# keyboard-Right.net
KiCad netlist of a schematic drawn in Altium Designer
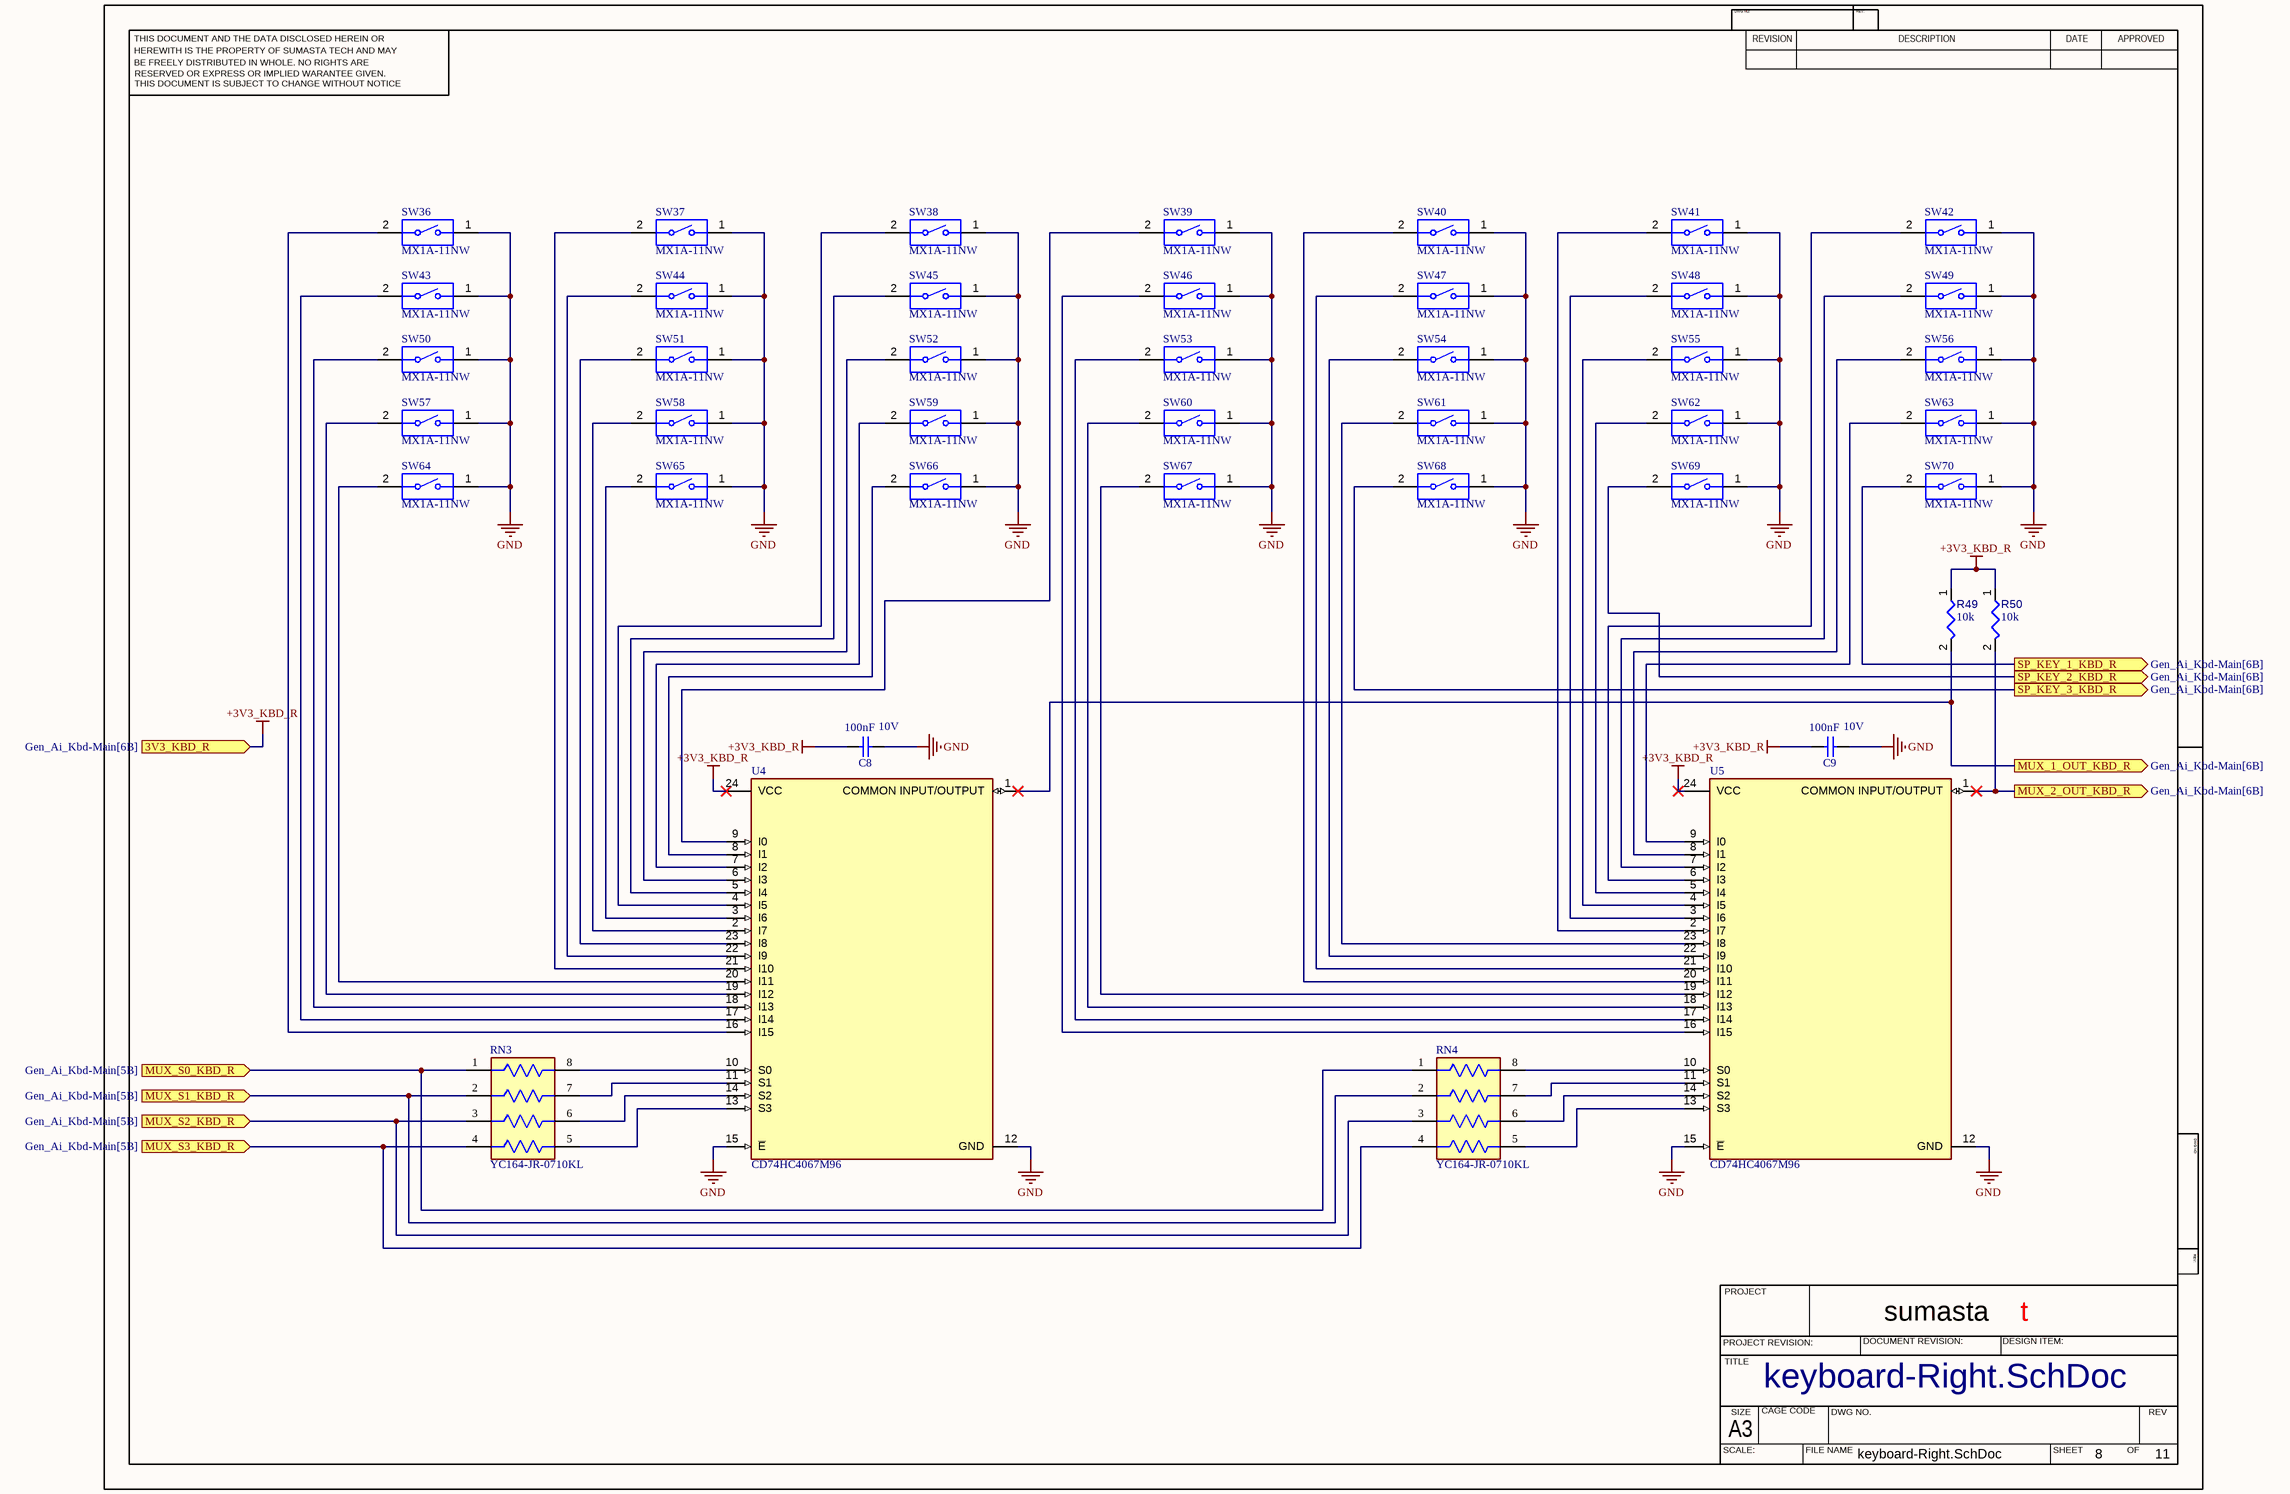
[diagram p0: keyboard-Right.SchDoc]

(export (version "E")
  (design (tool "Eeschema 10.0.6"))
  (components
    (comp (ref "C8")
      (value "885012206020")
      (footprint "WCAP-CSGP_0603_L1.6W0.8H0.8_Reflow")
      (description "WCAP-CSGP Multilayer Ceramic Chip Capacitor, General Purpose, size 0603, X7R, 100nF, 10VDC")
      (fields
        (field (name "MANUFACTURER") "Wurth Elektronik")
        (field (name "RATED VOLTAGE (DC)") "10V")
        (field (name "CAPACITANCE") "100nF")
      )
      (libsource (lib "Test365") (part "885012209047R"))
    )
    (comp (ref "C9")
      (value "885012206020")
      (footprint "WCAP-CSGP_0603_L1.6W0.8H0.8_Reflow")
      (description "WCAP-CSGP Multilayer Ceramic Chip Capacitor, General Purpose, size 0603, X7R, 100nF, 10VDC")
      (fields
        (field (name "MANUFACTURER") "Wurth Elektronik")
        (field (name "RATED VOLTAGE (DC)") "10V")
        (field (name "CAPACITANCE") "100nF")
      )
      (libsource (lib "Test365") (part "885012209047R"))
    )
    (comp (ref "R49")
      (value "10k")
      (footprint "RESC1608X55X25ML10T15")
      (description "Chip Resistor, 10 KOhm, +/- 1%, 01 W, -55 to 155 degC, 0603 (1608 Metric)")
      (fields (field (name "POWER") "100mW") (field (name "TOLERANCE") "1%"))
      (libsource (lib "Test365") (part "RES-2"))
    )
    (comp (ref "R50")
      (value "10k")
      (footprint "RESC1608X55X25ML10T15")
      (description "Chip Resistor, 10 KOhm, +/- 1%, 01 W, -55 to 155 degC, 0603 (1608 Metric)")
      (fields (field (name "POWER") "100mW") (field (name "TOLERANCE") "1%"))
      (libsource (lib "Test365") (part "RES-2"))
    )
    (comp (ref "RN3")
      (value "YC164-JR-0710KL")
      (footprint "FP-YC164-MFG")
      (description "RES ARRAY 4 RES 10K OHM 1206")
      (fields (field (name "TOLERANCE") "1%"))
      (libsource (lib "Altium Content Vault") (part "deefe693e103177f92eb02ee49083c3"))
    )
    (comp (ref "RN4")
      (value "YC164-JR-0710KL")
      (footprint "FP-YC164-MFG")
      (description "RES ARRAY 4 RES 10K OHM 1206")
      (fields (field (name "TOLERANCE") "1%"))
      (libsource (lib "Altium Content Vault") (part "deefe693e103177f92eb02ee49083c3"))
    )
    (comp (ref "SW36")
      (value "MX1A-11NW")
      (footprint "CHRY-MX1A-11NW_V")
      (description "Switch Key N.O. SPST 0.01A 12VAC 12VDC 0.58N PC Pins 50000000Cycles Thru-Hole")
      (libsource (lib "Test365") (part "KEYSW-SPST-2"))
    )
    (comp (ref "SW37")
      (value "MX1A-11NW")
      (footprint "CHRY-MX1A-11NW_V")
      (description "Switch Key N.O. SPST 0.01A 12VAC 12VDC 0.58N PC Pins 50000000Cycles Thru-Hole")
      (libsource (lib "Test365") (part "KEYSW-SPST-2"))
    )
    (comp (ref "SW38")
      (value "MX1A-11NW")
      (footprint "CHRY-MX1A-11NW_V")
      (description "Switch Key N.O. SPST 0.01A 12VAC 12VDC 0.58N PC Pins 50000000Cycles Thru-Hole")
      (libsource (lib "Test365") (part "KEYSW-SPST-2"))
    )
    (comp (ref "SW39")
      (value "MX1A-11NW")
      (footprint "CHRY-MX1A-11NW_V")
      (description "Switch Key N.O. SPST 0.01A 12VAC 12VDC 0.58N PC Pins 50000000Cycles Thru-Hole")
      (libsource (lib "Test365") (part "KEYSW-SPST-2"))
    )
    (comp (ref "SW40")
      (value "MX1A-11NW")
      (footprint "CHRY-MX1A-11NW_V")
      (description "Switch Key N.O. SPST 0.01A 12VAC 12VDC 0.58N PC Pins 50000000Cycles Thru-Hole")
      (libsource (lib "Test365") (part "KEYSW-SPST-2"))
    )
    (comp (ref "SW41")
      (value "MX1A-11NW")
      (footprint "CHRY-MX1A-11NW_V")
      (description "Switch Key N.O. SPST 0.01A 12VAC 12VDC 0.58N PC Pins 50000000Cycles Thru-Hole")
      (libsource (lib "Test365") (part "KEYSW-SPST-2"))
    )
    (comp (ref "SW42")
      (value "MX1A-11NW")
      (footprint "CHRY-MX1A-11NW_V")
      (description "Switch Key N.O. SPST 0.01A 12VAC 12VDC 0.58N PC Pins 50000000Cycles Thru-Hole")
      (libsource (lib "Test365") (part "KEYSW-SPST-2"))
    )
    (comp (ref "SW43")
      (value "MX1A-11NW")
      (footprint "CHRY-MX1A-11NW_V")
      (description "Switch Key N.O. SPST 0.01A 12VAC 12VDC 0.58N PC Pins 50000000Cycles Thru-Hole")
      (libsource (lib "Test365") (part "KEYSW-SPST-2"))
    )
    (comp (ref "SW44")
      (value "MX1A-11NW")
      (footprint "CHRY-MX1A-11NW_V")
      (description "Switch Key N.O. SPST 0.01A 12VAC 12VDC 0.58N PC Pins 50000000Cycles Thru-Hole")
      (libsource (lib "Test365") (part "KEYSW-SPST-2"))
    )
    (comp (ref "SW45")
      (value "MX1A-11NW")
      (footprint "CHRY-MX1A-11NW_V")
      (description "Switch Key N.O. SPST 0.01A 12VAC 12VDC 0.58N PC Pins 50000000Cycles Thru-Hole")
      (libsource (lib "Test365") (part "KEYSW-SPST-2"))
    )
    (comp (ref "SW46")
      (value "MX1A-11NW")
      (footprint "CHRY-MX1A-11NW_V")
      (description "Switch Key N.O. SPST 0.01A 12VAC 12VDC 0.58N PC Pins 50000000Cycles Thru-Hole")
      (libsource (lib "Test365") (part "KEYSW-SPST-2"))
    )
    (comp (ref "SW47")
      (value "MX1A-11NW")
      (footprint "CHRY-MX1A-11NW_V")
      (description "Switch Key N.O. SPST 0.01A 12VAC 12VDC 0.58N PC Pins 50000000Cycles Thru-Hole")
      (libsource (lib "Test365") (part "KEYSW-SPST-2"))
    )
    (comp (ref "SW48")
      (value "MX1A-11NW")
      (footprint "CHRY-MX1A-11NW_V")
      (description "Switch Key N.O. SPST 0.01A 12VAC 12VDC 0.58N PC Pins 50000000Cycles Thru-Hole")
      (libsource (lib "Test365") (part "KEYSW-SPST-2"))
    )
    (comp (ref "SW49")
      (value "MX1A-11NW")
      (footprint "CHRY-MX1A-11NW_V")
      (description "Switch Key N.O. SPST 0.01A 12VAC 12VDC 0.58N PC Pins 50000000Cycles Thru-Hole")
      (libsource (lib "Test365") (part "KEYSW-SPST-2"))
    )
    (comp (ref "SW50")
      (value "MX1A-11NW")
      (footprint "CHRY-MX1A-11NW_V")
      (description "Switch Key N.O. SPST 0.01A 12VAC 12VDC 0.58N PC Pins 50000000Cycles Thru-Hole")
      (libsource (lib "Test365") (part "KEYSW-SPST-2"))
    )
    (comp (ref "SW51")
      (value "MX1A-11NW")
      (footprint "CHRY-MX1A-11NW_V")
      (description "Switch Key N.O. SPST 0.01A 12VAC 12VDC 0.58N PC Pins 50000000Cycles Thru-Hole")
      (libsource (lib "Test365") (part "KEYSW-SPST-2"))
    )
    (comp (ref "SW52")
      (value "MX1A-11NW")
      (footprint "CHRY-MX1A-11NW_V")
      (description "Switch Key N.O. SPST 0.01A 12VAC 12VDC 0.58N PC Pins 50000000Cycles Thru-Hole")
      (libsource (lib "Test365") (part "KEYSW-SPST-2"))
    )
    (comp (ref "SW53")
      (value "MX1A-11NW")
      (footprint "CHRY-MX1A-11NW_V")
      (description "Switch Key N.O. SPST 0.01A 12VAC 12VDC 0.58N PC Pins 50000000Cycles Thru-Hole")
      (libsource (lib "Test365") (part "KEYSW-SPST-2"))
    )
    (comp (ref "SW54")
      (value "MX1A-11NW")
      (footprint "CHRY-MX1A-11NW_V")
      (description "Switch Key N.O. SPST 0.01A 12VAC 12VDC 0.58N PC Pins 50000000Cycles Thru-Hole")
      (libsource (lib "Test365") (part "KEYSW-SPST-2"))
    )
    (comp (ref "SW55")
      (value "MX1A-11NW")
      (footprint "CHRY-MX1A-11NW_V")
      (description "Switch Key N.O. SPST 0.01A 12VAC 12VDC 0.58N PC Pins 50000000Cycles Thru-Hole")
      (libsource (lib "Test365") (part "KEYSW-SPST-2"))
    )
    (comp (ref "SW56")
      (value "MX1A-11NW")
      (footprint "CHRY-MX1A-11NW_V")
      (description "Switch Key N.O. SPST 0.01A 12VAC 12VDC 0.58N PC Pins 50000000Cycles Thru-Hole")
      (libsource (lib "Test365") (part "KEYSW-SPST-2"))
    )
    (comp (ref "SW57")
      (value "MX1A-11NW")
      (footprint "CHRY-MX1A-11NW_V")
      (description "Switch Key N.O. SPST 0.01A 12VAC 12VDC 0.58N PC Pins 50000000Cycles Thru-Hole")
      (libsource (lib "Test365") (part "KEYSW-SPST-2"))
    )
    (comp (ref "SW58")
      (value "MX1A-11NW")
      (footprint "CHRY-MX1A-11NW_V")
      (description "Switch Key N.O. SPST 0.01A 12VAC 12VDC 0.58N PC Pins 50000000Cycles Thru-Hole")
      (libsource (lib "Test365") (part "KEYSW-SPST-2"))
    )
    (comp (ref "SW59")
      (value "MX1A-11NW")
      (footprint "CHRY-MX1A-11NW_V")
      (description "Switch Key N.O. SPST 0.01A 12VAC 12VDC 0.58N PC Pins 50000000Cycles Thru-Hole")
      (libsource (lib "Test365") (part "KEYSW-SPST-2"))
    )
    (comp (ref "SW60")
      (value "MX1A-11NW")
      (footprint "CHRY-MX1A-11NW_V")
      (description "Switch Key N.O. SPST 0.01A 12VAC 12VDC 0.58N PC Pins 50000000Cycles Thru-Hole")
      (libsource (lib "Test365") (part "KEYSW-SPST-2"))
    )
    (comp (ref "SW61")
      (value "MX1A-11NW")
      (footprint "CHRY-MX1A-11NW_V")
      (description "Switch Key N.O. SPST 0.01A 12VAC 12VDC 0.58N PC Pins 50000000Cycles Thru-Hole")
      (libsource (lib "Test365") (part "KEYSW-SPST-2"))
    )
    (comp (ref "SW62")
      (value "MX1A-11NW")
      (footprint "CHRY-MX1A-11NW_V")
      (description "Switch Key N.O. SPST 0.01A 12VAC 12VDC 0.58N PC Pins 50000000Cycles Thru-Hole")
      (libsource (lib "Test365") (part "KEYSW-SPST-2"))
    )
    (comp (ref "SW63")
      (value "MX1A-11NW")
      (footprint "CHRY-MX1A-11NW_V")
      (description "Switch Key N.O. SPST 0.01A 12VAC 12VDC 0.58N PC Pins 50000000Cycles Thru-Hole")
      (libsource (lib "Test365") (part "KEYSW-SPST-2"))
    )
    (comp (ref "SW64")
      (value "MX1A-11NW")
      (footprint "CHRY-MX1A-11NW_V")
      (description "Switch Key N.O. SPST 0.01A 12VAC 12VDC 0.58N PC Pins 50000000Cycles Thru-Hole")
      (libsource (lib "Test365") (part "KEYSW-SPST-2"))
    )
    (comp (ref "SW65")
      (value "MX1A-11NW")
      (footprint "CHRY-MX1A-11NW_V")
      (description "Switch Key N.O. SPST 0.01A 12VAC 12VDC 0.58N PC Pins 50000000Cycles Thru-Hole")
      (libsource (lib "Test365") (part "KEYSW-SPST-2"))
    )
    (comp (ref "SW66")
      (value "MX1A-11NW")
      (footprint "CHRY-MX1A-11NW_V")
      (description "Switch Key N.O. SPST 0.01A 12VAC 12VDC 0.58N PC Pins 50000000Cycles Thru-Hole")
      (libsource (lib "Test365") (part "KEYSW-SPST-2"))
    )
    (comp (ref "SW67")
      (value "MX1A-11NW")
      (footprint "CHRY-MX1A-11NW_V")
      (description "Switch Key N.O. SPST 0.01A 12VAC 12VDC 0.58N PC Pins 50000000Cycles Thru-Hole")
      (libsource (lib "Test365") (part "KEYSW-SPST-2"))
    )
    (comp (ref "SW68")
      (value "MX1A-11NW")
      (footprint "CHRY-MX1A-11NW_V")
      (description "Switch Key N.O. SPST 0.01A 12VAC 12VDC 0.58N PC Pins 50000000Cycles Thru-Hole")
      (libsource (lib "Test365") (part "KEYSW-SPST-2"))
    )
    (comp (ref "SW69")
      (value "MX1A-11NW")
      (footprint "CHRY-MX1A-11NW_V")
      (description "Switch Key N.O. SPST 0.01A 12VAC 12VDC 0.58N PC Pins 50000000Cycles Thru-Hole")
      (libsource (lib "Test365") (part "KEYSW-SPST-2"))
    )
    (comp (ref "SW70")
      (value "MX1A-11NW")
      (footprint "CHRY-MX1A-11NW_V")
      (description "Switch Key N.O. SPST 0.01A 12VAC 12VDC 0.58N PC Pins 50000000Cycles Thru-Hole")
      (libsource (lib "Test365") (part "KEYSW-SPST-2"))
    )
    (comp (ref "U4")
      (value "CD74HC4067M96")
      (footprint "FP-DW0024A-MFG")
      (description "IC MUX/DEMUX 1X16 24SOIC")
      (fields
        (field (name "OCTOPART") "https://octopart.com/cd74hc4067m96-texas+instruments-722802")
        (field (name "MANUFACTURER") "Texas Instruments")
      )
      (libsource (lib "Altium Content Vault") (part "0e3014a41e7f600214dac1b4fa06845"))
    )
    (comp (ref "U5")
      (value "CD74HC4067M96")
      (footprint "FP-DW0024A-MFG")
      (description "IC MUX/DEMUX 1X16 24SOIC")
      (fields
        (field (name "OCTOPART") "https://octopart.com/cd74hc4067m96-texas+instruments-722802")
        (field (name "MANUFACTURER") "Texas Instruments")
      )
      (libsource (lib "Altium Content Vault") (part "0e3014a41e7f600214dac1b4fa06845"))
    )
  )
  (nets
    (net (code "1") (name "+3V3_KBD_R") (class "Default")
      (node (ref "C8") (pin "1") (pinfunction "1_1") (pintype "passive"))
      (node (ref "C9") (pin "1") (pinfunction "1_1") (pintype "passive"))
      (node (ref "R49") (pin "1") (pinfunction "1_1") (pintype "passive"))
      (node (ref "R50") (pin "1") (pinfunction "1_1") (pintype "passive"))
      (node (ref "U4") (pin "24") (pinfunction "VCC_24") (pintype "power_in"))
      (node (ref "U5") (pin "24") (pinfunction "VCC_24") (pintype "power_in"))
    )
    (net (code "2") (name "/MUX_1_OUT_KBD_R") (class "Default")
      (node (ref "R49") (pin "2") (pinfunction "2_2") (pintype "passive"))
      (node (ref "U4") (pin "1") (pinfunction "COMMON_INPUT/OUTPUT_1") (pintype "bidirectional"))
    )
    (net (code "3") (name "/MUX_2_OUT_KBD_R") (class "Default")
      (node (ref "R50") (pin "2") (pinfunction "2_2") (pintype "passive"))
      (node (ref "U5") (pin "1") (pinfunction "COMMON_INPUT/OUTPUT_1") (pintype "bidirectional"))
    )
    (net (code "4") (name "/MUX_S0_KBD_R") (class "Default")
      (node (ref "RN3") (pin "1") (pinfunction "1_1") (pintype "passive"))
      (node (ref "RN4") (pin "1") (pinfunction "1_1") (pintype "passive"))
    )
    (net (code "5") (name "/MUX_S1_KBD_R") (class "Default")
      (node (ref "RN3") (pin "2") (pinfunction "2_2") (pintype "passive"))
      (node (ref "RN4") (pin "2") (pinfunction "2_2") (pintype "passive"))
    )
    (net (code "6") (name "/MUX_S2_KBD_R") (class "Default")
      (node (ref "RN3") (pin "3") (pinfunction "3_3") (pintype "passive"))
      (node (ref "RN4") (pin "3") (pinfunction "3_3") (pintype "passive"))
    )
    (net (code "7") (name "/MUX_S3_KBD_R") (class "Default")
      (node (ref "RN3") (pin "4") (pinfunction "4_4") (pintype "passive"))
      (node (ref "RN4") (pin "4") (pinfunction "4_4") (pintype "passive"))
    )
    (net (code "8") (name "/SP_KEY_1_KBD_R") (class "Default")
      (node (ref "SW70") (pin "2") (pinfunction "2_2") (pintype "passive"))
    )
    (net (code "9") (name "/SP_KEY_2_KBD_R") (class "Default")
      (node (ref "SW69") (pin "2") (pinfunction "2_2") (pintype "passive"))
    )
    (net (code "10") (name "/SP_KEY_3_KBD_R") (class "Default")
      (node (ref "SW68") (pin "2") (pinfunction "2_2") (pintype "passive"))
    )
    (net (code "11") (name "GND") (class "Default")
      (node (ref "C8") (pin "2") (pinfunction "2_2") (pintype "passive"))
      (node (ref "C9") (pin "2") (pinfunction "2_2") (pintype "passive"))
      (node (ref "SW36") (pin "1") (pinfunction "1_1") (pintype "passive"))
      (node (ref "SW37") (pin "1") (pinfunction "1_1") (pintype "passive"))
      (node (ref "SW38") (pin "1") (pinfunction "1_1") (pintype "passive"))
      (node (ref "SW39") (pin "1") (pinfunction "1_1") (pintype "passive"))
      (node (ref "SW40") (pin "1") (pinfunction "1_1") (pintype "passive"))
      (node (ref "SW41") (pin "1") (pinfunction "1_1") (pintype "passive"))
      (node (ref "SW42") (pin "1") (pinfunction "1_1") (pintype "passive"))
      (node (ref "SW43") (pin "1") (pinfunction "1_1") (pintype "passive"))
      (node (ref "SW44") (pin "1") (pinfunction "1_1") (pintype "passive"))
      (node (ref "SW45") (pin "1") (pinfunction "1_1") (pintype "passive"))
      (node (ref "SW46") (pin "1") (pinfunction "1_1") (pintype "passive"))
      (node (ref "SW47") (pin "1") (pinfunction "1_1") (pintype "passive"))
      (node (ref "SW48") (pin "1") (pinfunction "1_1") (pintype "passive"))
      (node (ref "SW49") (pin "1") (pinfunction "1_1") (pintype "passive"))
      (node (ref "SW50") (pin "1") (pinfunction "1_1") (pintype "passive"))
      (node (ref "SW51") (pin "1") (pinfunction "1_1") (pintype "passive"))
      (node (ref "SW52") (pin "1") (pinfunction "1_1") (pintype "passive"))
      (node (ref "SW53") (pin "1") (pinfunction "1_1") (pintype "passive"))
      (node (ref "SW54") (pin "1") (pinfunction "1_1") (pintype "passive"))
      (node (ref "SW55") (pin "1") (pinfunction "1_1") (pintype "passive"))
      (node (ref "SW56") (pin "1") (pinfunction "1_1") (pintype "passive"))
      (node (ref "SW57") (pin "1") (pinfunction "1_1") (pintype "passive"))
      (node (ref "SW58") (pin "1") (pinfunction "1_1") (pintype "passive"))
      (node (ref "SW59") (pin "1") (pinfunction "1_1") (pintype "passive"))
      (node (ref "SW60") (pin "1") (pinfunction "1_1") (pintype "passive"))
      (node (ref "SW61") (pin "1") (pinfunction "1_1") (pintype "passive"))
      (node (ref "SW62") (pin "1") (pinfunction "1_1") (pintype "passive"))
      (node (ref "SW63") (pin "1") (pinfunction "1_1") (pintype "passive"))
      (node (ref "SW64") (pin "1") (pinfunction "1_1") (pintype "passive"))
      (node (ref "SW65") (pin "1") (pinfunction "1_1") (pintype "passive"))
      (node (ref "SW66") (pin "1") (pinfunction "1_1") (pintype "passive"))
      (node (ref "SW67") (pin "1") (pinfunction "1_1") (pintype "passive"))
      (node (ref "SW68") (pin "1") (pinfunction "1_1") (pintype "passive"))
      (node (ref "SW69") (pin "1") (pinfunction "1_1") (pintype "passive"))
      (node (ref "SW70") (pin "1") (pinfunction "1_1") (pintype "passive"))
      (node (ref "U4") (pin "12") (pinfunction "GND_12") (pintype "power_in"))
      (node (ref "U4") (pin "15") (pinfunction "~{E}_15") (pintype "input"))
      (node (ref "U5") (pin "12") (pinfunction "GND_12") (pintype "power_in"))
      (node (ref "U5") (pin "15") (pinfunction "~{E}_15") (pintype "input"))
    )
    (net (code "12") (name "Net-(U4-I0)") (class "Default")
      (node (ref "SW39") (pin "2") (pinfunction "2_2") (pintype "passive"))
      (node (ref "U4") (pin "9") (pinfunction "I0_9") (pintype "input"))
    )
    (net (code "13") (name "Net-(U4-I1)") (class "Default")
      (node (ref "SW66") (pin "2") (pinfunction "2_2") (pintype "passive"))
      (node (ref "U4") (pin "8") (pinfunction "I1_8") (pintype "input"))
    )
    (net (code "14") (name "Net-(U4-I2)") (class "Default")
      (node (ref "SW59") (pin "2") (pinfunction "2_2") (pintype "passive"))
      (node (ref "U4") (pin "7") (pinfunction "I2_7") (pintype "input"))
    )
    (net (code "15") (name "Net-(U4-I3)") (class "Default")
      (node (ref "SW52") (pin "2") (pinfunction "2_2") (pintype "passive"))
      (node (ref "U4") (pin "6") (pinfunction "I3_6") (pintype "input"))
    )
    (net (code "16") (name "Net-(U4-I4)") (class "Default")
      (node (ref "SW45") (pin "2") (pinfunction "2_2") (pintype "passive"))
      (node (ref "U4") (pin "5") (pinfunction "I4_5") (pintype "input"))
    )
    (net (code "17") (name "Net-(U4-I5)") (class "Default")
      (node (ref "SW38") (pin "2") (pinfunction "2_2") (pintype "passive"))
      (node (ref "U4") (pin "4") (pinfunction "I5_4") (pintype "input"))
    )
    (net (code "18") (name "Net-(U4-I6)") (class "Default")
      (node (ref "SW65") (pin "2") (pinfunction "2_2") (pintype "passive"))
      (node (ref "U4") (pin "3") (pinfunction "I6_3") (pintype "input"))
    )
    (net (code "19") (name "Net-(U4-I7)") (class "Default")
      (node (ref "SW58") (pin "2") (pinfunction "2_2") (pintype "passive"))
      (node (ref "U4") (pin "2") (pinfunction "I7_2") (pintype "input"))
    )
    (net (code "20") (name "Net-(U4-I8)") (class "Default")
      (node (ref "SW51") (pin "2") (pinfunction "2_2") (pintype "passive"))
      (node (ref "U4") (pin "23") (pinfunction "I8_23") (pintype "input"))
    )
    (net (code "21") (name "Net-(U4-I9)") (class "Default")
      (node (ref "SW44") (pin "2") (pinfunction "2_2") (pintype "passive"))
      (node (ref "U4") (pin "22") (pinfunction "I9_22") (pintype "input"))
    )
    (net (code "22") (name "Net-(U4-I10)") (class "Default")
      (node (ref "SW37") (pin "2") (pinfunction "2_2") (pintype "passive"))
      (node (ref "U4") (pin "21") (pinfunction "I10_21") (pintype "input"))
    )
    (net (code "23") (name "Net-(U4-I11)") (class "Default")
      (node (ref "SW64") (pin "2") (pinfunction "2_2") (pintype "passive"))
      (node (ref "U4") (pin "20") (pinfunction "I11_20") (pintype "input"))
    )
    (net (code "24") (name "Net-(U4-I12)") (class "Default")
      (node (ref "SW57") (pin "2") (pinfunction "2_2") (pintype "passive"))
      (node (ref "U4") (pin "19") (pinfunction "I12_19") (pintype "input"))
    )
    (net (code "25") (name "Net-(U4-I13)") (class "Default")
      (node (ref "SW50") (pin "2") (pinfunction "2_2") (pintype "passive"))
      (node (ref "U4") (pin "18") (pinfunction "I13_18") (pintype "input"))
    )
    (net (code "26") (name "Net-(U4-I14)") (class "Default")
      (node (ref "SW43") (pin "2") (pinfunction "2_2") (pintype "passive"))
      (node (ref "U4") (pin "17") (pinfunction "I14_17") (pintype "input"))
    )
    (net (code "27") (name "Net-(U4-I15)") (class "Default")
      (node (ref "SW36") (pin "2") (pinfunction "2_2") (pintype "passive"))
      (node (ref "U4") (pin "16") (pinfunction "I15_16") (pintype "input"))
    )
    (net (code "28") (name "Net-(U4-S0)") (class "Default")
      (node (ref "RN3") (pin "8") (pinfunction "8_8") (pintype "passive"))
      (node (ref "U4") (pin "10") (pinfunction "S0_10") (pintype "input"))
    )
    (net (code "29") (name "Net-(U4-S1)") (class "Default")
      (node (ref "RN3") (pin "7") (pinfunction "7_7") (pintype "passive"))
      (node (ref "U4") (pin "11") (pinfunction "S1_11") (pintype "input"))
    )
    (net (code "30") (name "Net-(U4-S2)") (class "Default")
      (node (ref "RN3") (pin "6") (pinfunction "6_6") (pintype "passive"))
      (node (ref "U4") (pin "14") (pinfunction "S2_14") (pintype "input"))
    )
    (net (code "31") (name "Net-(U4-S3)") (class "Default")
      (node (ref "RN3") (pin "5") (pinfunction "5_5") (pintype "passive"))
      (node (ref "U4") (pin "13") (pinfunction "S3_13") (pintype "input"))
    )
    (net (code "32") (name "Net-(U5-I0)") (class "Default")
      (node (ref "SW63") (pin "2") (pinfunction "2_2") (pintype "passive"))
      (node (ref "U5") (pin "9") (pinfunction "I0_9") (pintype "input"))
    )
    (net (code "33") (name "Net-(U5-I1)") (class "Default")
      (node (ref "SW56") (pin "2") (pinfunction "2_2") (pintype "passive"))
      (node (ref "U5") (pin "8") (pinfunction "I1_8") (pintype "input"))
    )
    (net (code "34") (name "Net-(U5-I2)") (class "Default")
      (node (ref "SW49") (pin "2") (pinfunction "2_2") (pintype "passive"))
      (node (ref "U5") (pin "7") (pinfunction "I2_7") (pintype "input"))
    )
    (net (code "35") (name "Net-(U5-I3)") (class "Default")
      (node (ref "SW42") (pin "2") (pinfunction "2_2") (pintype "passive"))
      (node (ref "U5") (pin "6") (pinfunction "I3_6") (pintype "input"))
    )
    (net (code "36") (name "Net-(U5-I4)") (class "Default")
      (node (ref "SW62") (pin "2") (pinfunction "2_2") (pintype "passive"))
      (node (ref "U5") (pin "5") (pinfunction "I4_5") (pintype "input"))
    )
    (net (code "37") (name "Net-(U5-I5)") (class "Default")
      (node (ref "SW55") (pin "2") (pinfunction "2_2") (pintype "passive"))
      (node (ref "U5") (pin "4") (pinfunction "I5_4") (pintype "input"))
    )
    (net (code "38") (name "Net-(U5-I6)") (class "Default")
      (node (ref "SW48") (pin "2") (pinfunction "2_2") (pintype "passive"))
      (node (ref "U5") (pin "3") (pinfunction "I6_3") (pintype "input"))
    )
    (net (code "39") (name "Net-(U5-I7)") (class "Default")
      (node (ref "SW41") (pin "2") (pinfunction "2_2") (pintype "passive"))
      (node (ref "U5") (pin "2") (pinfunction "I7_2") (pintype "input"))
    )
    (net (code "40") (name "Net-(U5-I8)") (class "Default")
      (node (ref "SW61") (pin "2") (pinfunction "2_2") (pintype "passive"))
      (node (ref "U5") (pin "23") (pinfunction "I8_23") (pintype "input"))
    )
    (net (code "41") (name "Net-(U5-I9)") (class "Default")
      (node (ref "SW54") (pin "2") (pinfunction "2_2") (pintype "passive"))
      (node (ref "U5") (pin "22") (pinfunction "I9_22") (pintype "input"))
    )
    (net (code "42") (name "Net-(U5-I10)") (class "Default")
      (node (ref "SW47") (pin "2") (pinfunction "2_2") (pintype "passive"))
      (node (ref "U5") (pin "21") (pinfunction "I10_21") (pintype "input"))
    )
    (net (code "43") (name "Net-(U5-I11)") (class "Default")
      (node (ref "SW40") (pin "2") (pinfunction "2_2") (pintype "passive"))
      (node (ref "U5") (pin "20") (pinfunction "I11_20") (pintype "input"))
    )
    (net (code "44") (name "Net-(U5-I12)") (class "Default")
      (node (ref "SW67") (pin "2") (pinfunction "2_2") (pintype "passive"))
      (node (ref "U5") (pin "19") (pinfunction "I12_19") (pintype "input"))
    )
    (net (code "45") (name "Net-(U5-I13)") (class "Default")
      (node (ref "SW60") (pin "2") (pinfunction "2_2") (pintype "passive"))
      (node (ref "U5") (pin "18") (pinfunction "I13_18") (pintype "input"))
    )
    (net (code "46") (name "Net-(U5-I14)") (class "Default")
      (node (ref "SW53") (pin "2") (pinfunction "2_2") (pintype "passive"))
      (node (ref "U5") (pin "17") (pinfunction "I14_17") (pintype "input"))
    )
    (net (code "47") (name "Net-(U5-I15)") (class "Default")
      (node (ref "SW46") (pin "2") (pinfunction "2_2") (pintype "passive"))
      (node (ref "U5") (pin "16") (pinfunction "I15_16") (pintype "input"))
    )
    (net (code "48") (name "Net-(U5-S0)") (class "Default")
      (node (ref "RN4") (pin "8") (pinfunction "8_8") (pintype "passive"))
      (node (ref "U5") (pin "10") (pinfunction "S0_10") (pintype "input"))
    )
    (net (code "49") (name "Net-(U5-S1)") (class "Default")
      (node (ref "RN4") (pin "7") (pinfunction "7_7") (pintype "passive"))
      (node (ref "U5") (pin "11") (pinfunction "S1_11") (pintype "input"))
    )
    (net (code "50") (name "Net-(U5-S2)") (class "Default")
      (node (ref "RN4") (pin "6") (pinfunction "6_6") (pintype "passive"))
      (node (ref "U5") (pin "14") (pinfunction "S2_14") (pintype "input"))
    )
    (net (code "51") (name "Net-(U5-S3)") (class "Default")
      (node (ref "RN4") (pin "5") (pinfunction "5_5") (pintype "passive"))
      (node (ref "U5") (pin "13") (pinfunction "S3_13") (pintype "input"))
    )
  )
)
